# ext_breadboard_M.net
KiCad netlist of a schematic drawn in EAGLE
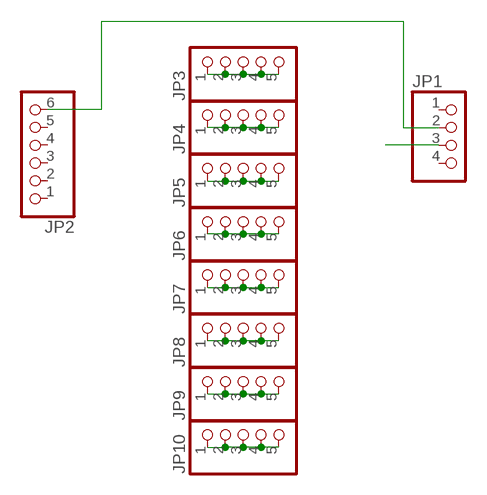
[diagram p0: schematic, sheet 1]

(export (version "E")
  (design (tool "Eeschema 10.0.6"))
  (components
    (comp (ref "JP1")
      (value "PINHD-1X4")
      (footprint "eagle-import:1X04")
      (libsource (lib "eagle-import") (part "PINHD-1X4"))
    )
    (comp (ref "JP2")
      (value "PINHD-1X6")
      (footprint "eagle-import:1X06")
      (libsource (lib "eagle-import") (part "PINHD-1X6"))
    )
    (comp (ref "JP3")
      (value "PINHD-1X5")
      (footprint "eagle-import:1X05")
      (libsource (lib "eagle-import") (part "PINHD-1X5"))
    )
    (comp (ref "JP4")
      (value "PINHD-1X5")
      (footprint "eagle-import:1X05")
      (libsource (lib "eagle-import") (part "PINHD-1X5"))
    )
    (comp (ref "JP5")
      (value "PINHD-1X5")
      (footprint "eagle-import:1X05")
      (libsource (lib "eagle-import") (part "PINHD-1X5"))
    )
    (comp (ref "JP6")
      (value "PINHD-1X5")
      (footprint "eagle-import:1X05")
      (libsource (lib "eagle-import") (part "PINHD-1X5"))
    )
    (comp (ref "JP7")
      (value "PINHD-1X5")
      (footprint "eagle-import:1X05")
      (libsource (lib "eagle-import") (part "PINHD-1X5"))
    )
    (comp (ref "JP8")
      (value "PINHD-1X5")
      (footprint "eagle-import:1X05")
      (libsource (lib "eagle-import") (part "PINHD-1X5"))
    )
    (comp (ref "JP9")
      (value "PINHD-1X5")
      (footprint "eagle-import:1X05")
      (libsource (lib "eagle-import") (part "PINHD-1X5"))
    )
    (comp (ref "JP10")
      (value "PINHD-1X5")
      (footprint "eagle-import:1X05")
      (libsource (lib "eagle-import") (part "PINHD-1X5"))
    )
  )
  (nets
    (net (code "1") (name "Net-(JP1-Pad2)") (class "Default")
      (node (ref "JP1") (pin "2") (pinfunction "2_2") (pintype "passive"))
      (node (ref "JP2") (pin "6") (pinfunction "6_6") (pintype "passive"))
    )
    (net (code "2") (name "Net-(JP3-Pad1)") (class "Default")
      (node (ref "JP3") (pin "1") (pinfunction "1_1") (pintype "passive"))
      (node (ref "JP3") (pin "2") (pinfunction "2_2") (pintype "passive"))
      (node (ref "JP3") (pin "3") (pinfunction "3_3") (pintype "passive"))
      (node (ref "JP3") (pin "4") (pinfunction "4_4") (pintype "passive"))
      (node (ref "JP3") (pin "5") (pinfunction "5_5") (pintype "passive"))
    )
    (net (code "3") (name "Net-(JP4-Pad1)") (class "Default")
      (node (ref "JP4") (pin "1") (pinfunction "1_1") (pintype "passive"))
      (node (ref "JP4") (pin "2") (pinfunction "2_2") (pintype "passive"))
      (node (ref "JP4") (pin "3") (pinfunction "3_3") (pintype "passive"))
      (node (ref "JP4") (pin "4") (pinfunction "4_4") (pintype "passive"))
      (node (ref "JP4") (pin "5") (pinfunction "5_5") (pintype "passive"))
    )
    (net (code "4") (name "Net-(JP5-Pad1)") (class "Default")
      (node (ref "JP5") (pin "1") (pinfunction "1_1") (pintype "passive"))
      (node (ref "JP5") (pin "2") (pinfunction "2_2") (pintype "passive"))
      (node (ref "JP5") (pin "3") (pinfunction "3_3") (pintype "passive"))
      (node (ref "JP5") (pin "4") (pinfunction "4_4") (pintype "passive"))
      (node (ref "JP5") (pin "5") (pinfunction "5_5") (pintype "passive"))
    )
    (net (code "5") (name "Net-(JP6-Pad1)") (class "Default")
      (node (ref "JP6") (pin "1") (pinfunction "1_1") (pintype "passive"))
      (node (ref "JP6") (pin "2") (pinfunction "2_2") (pintype "passive"))
      (node (ref "JP6") (pin "3") (pinfunction "3_3") (pintype "passive"))
      (node (ref "JP6") (pin "4") (pinfunction "4_4") (pintype "passive"))
      (node (ref "JP6") (pin "5") (pinfunction "5_5") (pintype "passive"))
    )
    (net (code "6") (name "Net-(JP7-Pad1)") (class "Default")
      (node (ref "JP7") (pin "1") (pinfunction "1_1") (pintype "passive"))
      (node (ref "JP7") (pin "2") (pinfunction "2_2") (pintype "passive"))
      (node (ref "JP7") (pin "3") (pinfunction "3_3") (pintype "passive"))
      (node (ref "JP7") (pin "4") (pinfunction "4_4") (pintype "passive"))
      (node (ref "JP7") (pin "5") (pinfunction "5_5") (pintype "passive"))
    )
    (net (code "7") (name "Net-(JP8-Pad1)") (class "Default")
      (node (ref "JP8") (pin "1") (pinfunction "1_1") (pintype "passive"))
      (node (ref "JP8") (pin "2") (pinfunction "2_2") (pintype "passive"))
      (node (ref "JP8") (pin "3") (pinfunction "3_3") (pintype "passive"))
      (node (ref "JP8") (pin "4") (pinfunction "4_4") (pintype "passive"))
      (node (ref "JP8") (pin "5") (pinfunction "5_5") (pintype "passive"))
    )
    (net (code "8") (name "Net-(JP9-Pad1)") (class "Default")
      (node (ref "JP9") (pin "1") (pinfunction "1_1") (pintype "passive"))
      (node (ref "JP9") (pin "2") (pinfunction "2_2") (pintype "passive"))
      (node (ref "JP9") (pin "3") (pinfunction "3_3") (pintype "passive"))
      (node (ref "JP9") (pin "4") (pinfunction "4_4") (pintype "passive"))
      (node (ref "JP9") (pin "5") (pinfunction "5_5") (pintype "passive"))
    )
    (net (code "9") (name "Net-(JP10-Pad1)") (class "Default")
      (node (ref "JP10") (pin "1") (pinfunction "1_1") (pintype "passive"))
      (node (ref "JP10") (pin "2") (pinfunction "2_2") (pintype "passive"))
      (node (ref "JP10") (pin "3") (pinfunction "3_3") (pintype "passive"))
      (node (ref "JP10") (pin "4") (pinfunction "4_4") (pintype "passive"))
      (node (ref "JP10") (pin "5") (pinfunction "5_5") (pintype "passive"))
    )
    (net (code "10") (name "unconnected-(JP1-Pad1)") (class "Default")
      (node (ref "JP1") (pin "1") (pinfunction "1_1") (pintype "passive"))
    )
    (net (code "11") (name "unconnected-(JP1-Pad3)") (class "Default")
      (node (ref "JP1") (pin "3") (pinfunction "3_3") (pintype "passive"))
    )
    (net (code "12") (name "unconnected-(JP1-Pad4)") (class "Default")
      (node (ref "JP1") (pin "4") (pinfunction "4_4") (pintype "passive"))
    )
    (net (code "13") (name "unconnected-(JP2-Pad1)") (class "Default")
      (node (ref "JP2") (pin "1") (pinfunction "1_1") (pintype "passive"))
    )
    (net (code "14") (name "unconnected-(JP2-Pad2)") (class "Default")
      (node (ref "JP2") (pin "2") (pinfunction "2_2") (pintype "passive"))
    )
    (net (code "15") (name "unconnected-(JP2-Pad3)") (class "Default")
      (node (ref "JP2") (pin "3") (pinfunction "3_3") (pintype "passive"))
    )
    (net (code "16") (name "unconnected-(JP2-Pad4)") (class "Default")
      (node (ref "JP2") (pin "4") (pinfunction "4_4") (pintype "passive"))
    )
    (net (code "17") (name "unconnected-(JP2-Pad5)") (class "Default")
      (node (ref "JP2") (pin "5") (pinfunction "5_5") (pintype "passive"))
    )
  )
)
